# Fan_Control_Test.net
KiCad netlist of a schematic drawn in EAGLE
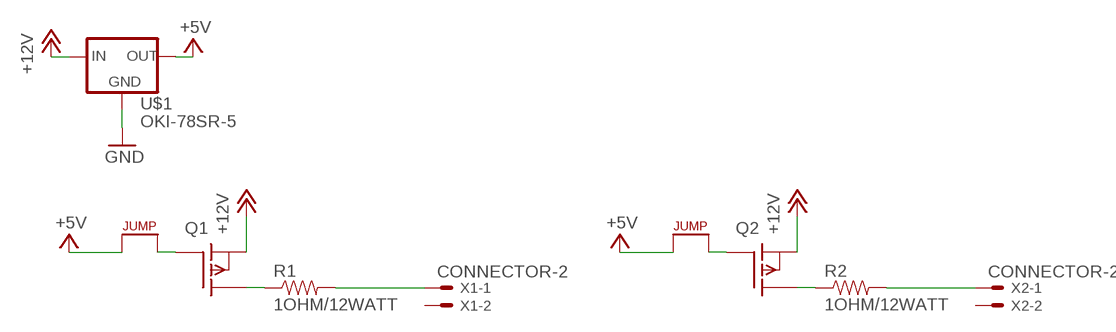
[diagram p0: schematic, sheet 1]

(export (version "E")
  (design (tool "Eeschema 10.0.6"))
  (components
    (comp (ref "J1")
      (value "JUMPER.1")
      (footprint "eagle-import:1X02")
      (libsource (lib "eagle-import") (part "JUMPER.1"))
    )
    (comp (ref "J3")
      (value "JUMPER.1")
      (footprint "eagle-import:1X02")
      (libsource (lib "eagle-import") (part "JUMPER.1"))
    )
    (comp (ref "Q1")
      (value "P-CHANNEL_MOSFET_DMP3099L-7")
      (footprint "eagle-import:SOT23")
      (libsource (lib "eagle-import") (part "P-CHANNEL_MOSFET_DMP3099L-7"))
    )
    (comp (ref "Q2")
      (value "P-CHANNEL_MOSFET_DMP3099L-7")
      (footprint "eagle-import:SOT23")
      (libsource (lib "eagle-import") (part "P-CHANNEL_MOSFET_DMP3099L-7"))
    )
    (comp (ref "R1")
      (value "1OHM/12WATT")
      (footprint "eagle-import:10W_RESISTOR_VISHAY")
      (libsource (lib "eagle-import") (part "RESISTOR10W"))
    )
    (comp (ref "R2")
      (value "1OHM/12WATT")
      (footprint "eagle-import:10W_RESISTOR_VISHAY")
      (libsource (lib "eagle-import") (part "RESISTOR10W"))
    )
    (comp (ref "U$1")
      (value "OKI-78SR-5")
      (footprint "eagle-import:OKI-78SR")
      (libsource (lib "eagle-import") (part "OKI-78SR-5"))
    )
    (comp (ref "X1")
      (value "CONNECTOR-2")
      (footprint "eagle-import:MINIFIT_5566-2")
      (libsource (lib "eagle-import") (part "CONNECTOR-2"))
    )
    (comp (ref "X2")
      (value "CONNECTOR-2")
      (footprint "eagle-import:MINIFIT_5566-2")
      (libsource (lib "eagle-import") (part "CONNECTOR-2"))
    )
  )
  (nets
    (net (code "1") (name "+5V") (class "Default")
      (node (ref "J1") (pin "1") (pinfunction "P$1_1") (pintype "bidirectional"))
      (node (ref "J3") (pin "1") (pinfunction "P$1_1") (pintype "bidirectional"))
      (node (ref "U$1") (pin "3") (pinfunction "OUT_3") (pintype "passive"))
    )
    (net (code "2") (name "+12V") (class "Default")
      (node (ref "Q1") (pin "2") (pinfunction "S_2") (pintype "passive"))
      (node (ref "Q2") (pin "2") (pinfunction "S_2") (pintype "passive"))
      (node (ref "U$1") (pin "1") (pinfunction "IN_1") (pintype "input"))
    )
    (net (code "3") (name "GND") (class "Default")
      (node (ref "U$1") (pin "2") (pinfunction "GND_2") (pintype "input"))
    )
    (net (code "4") (name "Net-(J1-P$2)") (class "Default")
      (node (ref "J1") (pin "2") (pinfunction "P$2_2") (pintype "bidirectional"))
      (node (ref "Q1") (pin "1") (pinfunction "G_1") (pintype "passive"))
    )
    (net (code "5") (name "Net-(J3-P$2)") (class "Default")
      (node (ref "J3") (pin "2") (pinfunction "P$2_2") (pintype "bidirectional"))
      (node (ref "Q2") (pin "1") (pinfunction "G_1") (pintype "passive"))
    )
    (net (code "6") (name "Net-(Q1-D)") (class "Default")
      (node (ref "Q1") (pin "3") (pinfunction "D_3") (pintype "passive"))
      (node (ref "R1") (pin "1") (pinfunction "1_1") (pintype "passive"))
    )
    (net (code "7") (name "Net-(Q2-D)") (class "Default")
      (node (ref "Q2") (pin "3") (pinfunction "D_3") (pintype "passive"))
      (node (ref "R2") (pin "1") (pinfunction "1_1") (pintype "passive"))
    )
    (net (code "8") (name "Net-(X1A-S)") (class "Default")
      (node (ref "R1") (pin "2") (pinfunction "2_2") (pintype "passive"))
      (node (ref "X1") (pin "1") (pinfunction "S_1") (pintype "passive"))
    )
    (net (code "9") (name "Net-(X2A-S)") (class "Default")
      (node (ref "R2") (pin "2") (pinfunction "2_2") (pintype "passive"))
      (node (ref "X2") (pin "1") (pinfunction "S_1") (pintype "passive"))
    )
    (net (code "10") (name "unconnected-(X1B-S-Pad2)") (class "Default")
      (node (ref "X1") (pin "2") (pinfunction "S_2") (pintype "passive"))
    )
    (net (code "11") (name "unconnected-(X2B-S-Pad2)") (class "Default")
      (node (ref "X2") (pin "2") (pinfunction "S_2") (pintype "passive"))
    )
  )
)
